# Optocoupler_STM32_REVB.net
KiCad netlist of a schematic drawn in Altium Designer
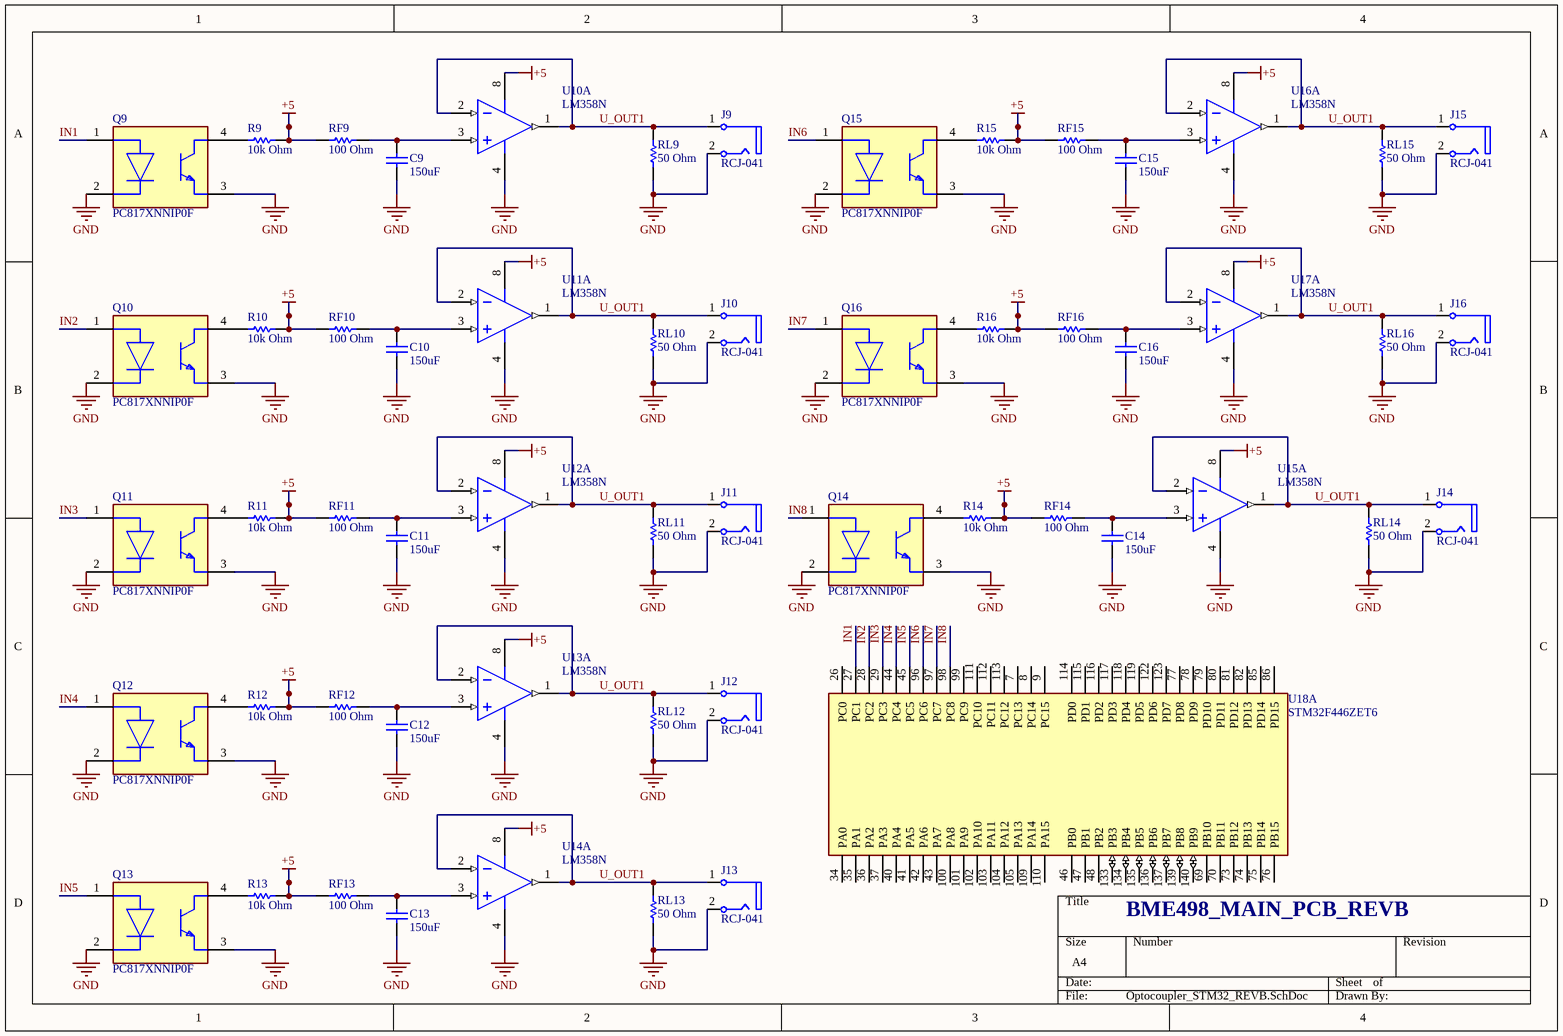
[diagram p0: Optocoupler_STM32_REVB.SchDoc]

(export (version "E")
  (design (tool "Eeschema 10.0.6"))
  (components
    (comp (ref "C9")
      (value "150uF")
      (footprint "RADIAL-0.1")
      (description "Capacitor")
      (fields
        (field (name "MANUFACTURER PART NUMBER") "EEA-GA1C150B")
        (field (name "PUBLISHER") "Altium Limited")
      )
      (libsource (lib "ECE295-Capacitors-TH") (part "CAP ALUM 15UF 20% 16V RADIAL"))
    )
    (comp (ref "C10")
      (value "150uF")
      (footprint "RADIAL-0.1")
      (description "Capacitor")
      (fields
        (field (name "MANUFACTURER PART NUMBER") "EEA-GA1C150B")
        (field (name "PUBLISHER") "Altium Limited")
      )
      (libsource (lib "ECE295-Capacitors-TH") (part "CAP ALUM 15UF 20% 16V RADIAL"))
    )
    (comp (ref "C11")
      (value "150uF")
      (footprint "RADIAL-0.1")
      (description "Capacitor")
      (fields
        (field (name "MANUFACTURER PART NUMBER") "EEA-GA1C150B")
        (field (name "PUBLISHER") "Altium Limited")
      )
      (libsource (lib "ECE295-Capacitors-TH") (part "CAP ALUM 15UF 20% 16V RADIAL"))
    )
    (comp (ref "C12")
      (value "150uF")
      (footprint "RADIAL-0.1")
      (description "Capacitor")
      (fields
        (field (name "MANUFACTURER PART NUMBER") "EEA-GA1C150B")
        (field (name "PUBLISHER") "Altium Limited")
      )
      (libsource (lib "ECE295-Capacitors-TH") (part "CAP ALUM 15UF 20% 16V RADIAL"))
    )
    (comp (ref "C13")
      (value "150uF")
      (footprint "RADIAL-0.1")
      (description "Capacitor")
      (fields
        (field (name "MANUFACTURER PART NUMBER") "EEA-GA1C150B")
        (field (name "PUBLISHER") "Altium Limited")
      )
      (libsource (lib "ECE295-Capacitors-TH") (part "CAP ALUM 15UF 20% 16V RADIAL"))
    )
    (comp (ref "C14")
      (value "150uF")
      (footprint "RADIAL-0.1")
      (description "Capacitor")
      (fields
        (field (name "MANUFACTURER PART NUMBER") "EEA-GA1C150B")
        (field (name "PUBLISHER") "Altium Limited")
      )
      (libsource (lib "ECE295-Capacitors-TH") (part "CAP ALUM 15UF 20% 16V RADIAL"))
    )
    (comp (ref "C15")
      (value "150uF")
      (footprint "RADIAL-0.1")
      (description "Capacitor")
      (fields
        (field (name "MANUFACTURER PART NUMBER") "EEA-GA1C150B")
        (field (name "PUBLISHER") "Altium Limited")
      )
      (libsource (lib "ECE295-Capacitors-TH") (part "CAP ALUM 15UF 20% 16V RADIAL"))
    )
    (comp (ref "C16")
      (value "150uF")
      (footprint "RADIAL-0.1")
      (description "Capacitor")
      (fields
        (field (name "MANUFACTURER PART NUMBER") "EEA-GA1C150B")
        (field (name "PUBLISHER") "Altium Limited")
      )
      (libsource (lib "ECE295-Capacitors-TH") (part "CAP ALUM 15UF 20% 16V RADIAL"))
    )
    (comp (ref "J9")
      (value "RCJ-041")
      (footprint "CUI-RCJ-041_V")
      (description "Female RCJ Jack, 2 Position, Height 11.724 mm, Tail Length 4 mm, RoHS, Bulk")
      (libsource (lib "Altium Content Vault") (part "JACK-2CD2"))
    )
    (comp (ref "J10")
      (value "RCJ-041")
      (footprint "CUI-RCJ-041_V")
      (description "Female RCJ Jack, 2 Position, Height 11.724 mm, Tail Length 4 mm, RoHS, Bulk")
      (libsource (lib "Altium Content Vault") (part "JACK-2CD2"))
    )
    (comp (ref "J11")
      (value "RCJ-041")
      (footprint "CUI-RCJ-041_V")
      (description "Female RCJ Jack, 2 Position, Height 11.724 mm, Tail Length 4 mm, RoHS, Bulk")
      (libsource (lib "Altium Content Vault") (part "JACK-2CD2"))
    )
    (comp (ref "J12")
      (value "RCJ-041")
      (footprint "CUI-RCJ-041_V")
      (description "Female RCJ Jack, 2 Position, Height 11.724 mm, Tail Length 4 mm, RoHS, Bulk")
      (libsource (lib "Altium Content Vault") (part "JACK-2CD2"))
    )
    (comp (ref "J13")
      (value "RCJ-041")
      (footprint "CUI-RCJ-041_V")
      (description "Female RCJ Jack, 2 Position, Height 11.724 mm, Tail Length 4 mm, RoHS, Bulk")
      (libsource (lib "Altium Content Vault") (part "JACK-2CD2"))
    )
    (comp (ref "J14")
      (value "RCJ-041")
      (footprint "CUI-RCJ-041_V")
      (description "Female RCJ Jack, 2 Position, Height 11.724 mm, Tail Length 4 mm, RoHS, Bulk")
      (libsource (lib "Altium Content Vault") (part "JACK-2CD2"))
    )
    (comp (ref "J15")
      (value "RCJ-041")
      (footprint "CUI-RCJ-041_V")
      (description "Female RCJ Jack, 2 Position, Height 11.724 mm, Tail Length 4 mm, RoHS, Bulk")
      (libsource (lib "Altium Content Vault") (part "JACK-2CD2"))
    )
    (comp (ref "J16")
      (value "RCJ-041")
      (footprint "CUI-RCJ-041_V")
      (description "Female RCJ Jack, 2 Position, Height 11.724 mm, Tail Length 4 mm, RoHS, Bulk")
      (libsource (lib "Altium Content Vault") (part "JACK-2CD2"))
    )
    (comp (ref "Q9")
      (value "PC817XNNIP0F")
      (footprint "FP-PC817XNNIP0F-MFG")
      (description "OPTOISOLATOR 5KV TRANS 4SMD")
      (libsource (lib "Altium Content Vault") (part "6470904bf6395c62928ee73e60120b8"))
    )
    (comp (ref "Q10")
      (value "PC817XNNIP0F")
      (footprint "FP-PC817XNNIP0F-MFG")
      (description "OPTOISOLATOR 5KV TRANS 4SMD")
      (libsource (lib "Altium Content Vault") (part "6470904bf6395c62928ee73e60120b8"))
    )
    (comp (ref "Q11")
      (value "PC817XNNIP0F")
      (footprint "FP-PC817XNNIP0F-MFG")
      (description "OPTOISOLATOR 5KV TRANS 4SMD")
      (libsource (lib "Altium Content Vault") (part "6470904bf6395c62928ee73e60120b8"))
    )
    (comp (ref "Q12")
      (value "PC817XNNIP0F")
      (footprint "FP-PC817XNNIP0F-MFG")
      (description "OPTOISOLATOR 5KV TRANS 4SMD")
      (libsource (lib "Altium Content Vault") (part "6470904bf6395c62928ee73e60120b8"))
    )
    (comp (ref "Q13")
      (value "PC817XNNIP0F")
      (footprint "FP-PC817XNNIP0F-MFG")
      (description "OPTOISOLATOR 5KV TRANS 4SMD")
      (libsource (lib "Altium Content Vault") (part "6470904bf6395c62928ee73e60120b8"))
    )
    (comp (ref "Q14")
      (value "PC817XNNIP0F")
      (footprint "FP-PC817XNNIP0F-MFG")
      (description "OPTOISOLATOR 5KV TRANS 4SMD")
      (libsource (lib "Altium Content Vault") (part "6470904bf6395c62928ee73e60120b8"))
    )
    (comp (ref "Q15")
      (value "PC817XNNIP0F")
      (footprint "FP-PC817XNNIP0F-MFG")
      (description "OPTOISOLATOR 5KV TRANS 4SMD")
      (libsource (lib "Altium Content Vault") (part "6470904bf6395c62928ee73e60120b8"))
    )
    (comp (ref "Q16")
      (value "PC817XNNIP0F")
      (footprint "FP-PC817XNNIP0F-MFG")
      (description "OPTOISOLATOR 5KV TRANS 4SMD")
      (libsource (lib "Altium Content Vault") (part "6470904bf6395c62928ee73e60120b8"))
    )
    (comp (ref "R9")
      (value "10k Ohm")
      (footprint "AXIAL-0.3")
      (description "Resistor")
      (fields
        (field (name "MANUFACTURER PART NUMBER") "CFR-25JB-52-10R")
        (field (name "TOLERANCE") "0.05")
        (field (name "PUBLISHER") "Altium Limited")
      )
      (libsource (lib "ECE295-Resistors-TH") (part "RES 10 OHM 5% 1/4W AXIAL"))
    )
    (comp (ref "R10")
      (value "10k Ohm")
      (footprint "AXIAL-0.3")
      (description "Resistor")
      (fields
        (field (name "MANUFACTURER PART NUMBER") "CFR-25JB-52-10R")
        (field (name "TOLERANCE") "0.05")
        (field (name "PUBLISHER") "Altium Limited")
      )
      (libsource (lib "ECE295-Resistors-TH") (part "RES 10 OHM 5% 1/4W AXIAL"))
    )
    (comp (ref "R11")
      (value "10k Ohm")
      (footprint "AXIAL-0.3")
      (description "Resistor")
      (fields
        (field (name "MANUFACTURER PART NUMBER") "CFR-25JB-52-10R")
        (field (name "TOLERANCE") "0.05")
        (field (name "PUBLISHER") "Altium Limited")
      )
      (libsource (lib "ECE295-Resistors-TH") (part "RES 10 OHM 5% 1/4W AXIAL"))
    )
    (comp (ref "R12")
      (value "10k Ohm")
      (footprint "AXIAL-0.3")
      (description "Resistor")
      (fields
        (field (name "MANUFACTURER PART NUMBER") "CFR-25JB-52-10R")
        (field (name "TOLERANCE") "0.05")
        (field (name "PUBLISHER") "Altium Limited")
      )
      (libsource (lib "ECE295-Resistors-TH") (part "RES 10 OHM 5% 1/4W AXIAL"))
    )
    (comp (ref "R13")
      (value "10k Ohm")
      (footprint "AXIAL-0.3")
      (description "Resistor")
      (fields
        (field (name "MANUFACTURER PART NUMBER") "CFR-25JB-52-10R")
        (field (name "TOLERANCE") "0.05")
        (field (name "PUBLISHER") "Altium Limited")
      )
      (libsource (lib "ECE295-Resistors-TH") (part "RES 10 OHM 5% 1/4W AXIAL"))
    )
    (comp (ref "R14")
      (value "10k Ohm")
      (footprint "AXIAL-0.3")
      (description "Resistor")
      (fields
        (field (name "MANUFACTURER PART NUMBER") "CFR-25JB-52-10R")
        (field (name "TOLERANCE") "0.05")
        (field (name "PUBLISHER") "Altium Limited")
      )
      (libsource (lib "ECE295-Resistors-TH") (part "RES 10 OHM 5% 1/4W AXIAL"))
    )
    (comp (ref "R15")
      (value "10k Ohm")
      (footprint "AXIAL-0.3")
      (description "Resistor")
      (fields
        (field (name "MANUFACTURER PART NUMBER") "CFR-25JB-52-10R")
        (field (name "TOLERANCE") "0.05")
        (field (name "PUBLISHER") "Altium Limited")
      )
      (libsource (lib "ECE295-Resistors-TH") (part "RES 10 OHM 5% 1/4W AXIAL"))
    )
    (comp (ref "R16")
      (value "10k Ohm")
      (footprint "AXIAL-0.3")
      (description "Resistor")
      (fields
        (field (name "MANUFACTURER PART NUMBER") "CFR-25JB-52-10R")
        (field (name "TOLERANCE") "0.05")
        (field (name "PUBLISHER") "Altium Limited")
      )
      (libsource (lib "ECE295-Resistors-TH") (part "RES 10 OHM 5% 1/4W AXIAL"))
    )
    (comp (ref "RF9")
      (value "100 Ohm")
      (footprint "AXIAL-0.3")
      (description "Resistor")
      (fields
        (field (name "MANUFACTURER PART NUMBER") "CFR-25JB-52-10R")
        (field (name "TOLERANCE") "0.05")
        (field (name "PUBLISHER") "Altium Limited")
      )
      (libsource (lib "ECE295-Resistors-TH") (part "RES 10 OHM 5% 1/4W AXIAL"))
    )
    (comp (ref "RF10")
      (value "100 Ohm")
      (footprint "AXIAL-0.3")
      (description "Resistor")
      (fields
        (field (name "MANUFACTURER PART NUMBER") "CFR-25JB-52-10R")
        (field (name "TOLERANCE") "0.05")
        (field (name "PUBLISHER") "Altium Limited")
      )
      (libsource (lib "ECE295-Resistors-TH") (part "RES 10 OHM 5% 1/4W AXIAL"))
    )
    (comp (ref "RF11")
      (value "100 Ohm")
      (footprint "AXIAL-0.3")
      (description "Resistor")
      (fields
        (field (name "MANUFACTURER PART NUMBER") "CFR-25JB-52-10R")
        (field (name "TOLERANCE") "0.05")
        (field (name "PUBLISHER") "Altium Limited")
      )
      (libsource (lib "ECE295-Resistors-TH") (part "RES 10 OHM 5% 1/4W AXIAL"))
    )
    (comp (ref "RF12")
      (value "100 Ohm")
      (footprint "AXIAL-0.3")
      (description "Resistor")
      (fields
        (field (name "MANUFACTURER PART NUMBER") "CFR-25JB-52-10R")
        (field (name "TOLERANCE") "0.05")
        (field (name "PUBLISHER") "Altium Limited")
      )
      (libsource (lib "ECE295-Resistors-TH") (part "RES 10 OHM 5% 1/4W AXIAL"))
    )
    (comp (ref "RF13")
      (value "100 Ohm")
      (footprint "AXIAL-0.3")
      (description "Resistor")
      (fields
        (field (name "MANUFACTURER PART NUMBER") "CFR-25JB-52-10R")
        (field (name "TOLERANCE") "0.05")
        (field (name "PUBLISHER") "Altium Limited")
      )
      (libsource (lib "ECE295-Resistors-TH") (part "RES 10 OHM 5% 1/4W AXIAL"))
    )
    (comp (ref "RF14")
      (value "100 Ohm")
      (footprint "AXIAL-0.3")
      (description "Resistor")
      (fields
        (field (name "MANUFACTURER PART NUMBER") "CFR-25JB-52-10R")
        (field (name "TOLERANCE") "0.05")
        (field (name "PUBLISHER") "Altium Limited")
      )
      (libsource (lib "ECE295-Resistors-TH") (part "RES 10 OHM 5% 1/4W AXIAL"))
    )
    (comp (ref "RF15")
      (value "100 Ohm")
      (footprint "AXIAL-0.3")
      (description "Resistor")
      (fields
        (field (name "MANUFACTURER PART NUMBER") "CFR-25JB-52-10R")
        (field (name "TOLERANCE") "0.05")
        (field (name "PUBLISHER") "Altium Limited")
      )
      (libsource (lib "ECE295-Resistors-TH") (part "RES 10 OHM 5% 1/4W AXIAL"))
    )
    (comp (ref "RF16")
      (value "100 Ohm")
      (footprint "AXIAL-0.3")
      (description "Resistor")
      (fields
        (field (name "MANUFACTURER PART NUMBER") "CFR-25JB-52-10R")
        (field (name "TOLERANCE") "0.05")
        (field (name "PUBLISHER") "Altium Limited")
      )
      (libsource (lib "ECE295-Resistors-TH") (part "RES 10 OHM 5% 1/4W AXIAL"))
    )
    (comp (ref "RL9")
      (value "50 Ohm")
      (footprint "AXIAL-0.3")
      (description "Resistor")
      (fields
        (field (name "MANUFACTURER PART NUMBER") "CFR-25JB-52-10R")
        (field (name "TOLERANCE") "0.05")
        (field (name "PUBLISHER") "Altium Limited")
      )
      (libsource (lib "ECE295-Resistors-TH") (part "RES 10 OHM 5% 1/4W AXIAL"))
    )
    (comp (ref "RL10")
      (value "50 Ohm")
      (footprint "AXIAL-0.3")
      (description "Resistor")
      (fields
        (field (name "MANUFACTURER PART NUMBER") "CFR-25JB-52-10R")
        (field (name "TOLERANCE") "0.05")
        (field (name "PUBLISHER") "Altium Limited")
      )
      (libsource (lib "ECE295-Resistors-TH") (part "RES 10 OHM 5% 1/4W AXIAL"))
    )
    (comp (ref "RL11")
      (value "50 Ohm")
      (footprint "AXIAL-0.3")
      (description "Resistor")
      (fields
        (field (name "MANUFACTURER PART NUMBER") "CFR-25JB-52-10R")
        (field (name "TOLERANCE") "0.05")
        (field (name "PUBLISHER") "Altium Limited")
      )
      (libsource (lib "ECE295-Resistors-TH") (part "RES 10 OHM 5% 1/4W AXIAL"))
    )
    (comp (ref "RL12")
      (value "50 Ohm")
      (footprint "AXIAL-0.3")
      (description "Resistor")
      (fields
        (field (name "MANUFACTURER PART NUMBER") "CFR-25JB-52-10R")
        (field (name "TOLERANCE") "0.05")
        (field (name "PUBLISHER") "Altium Limited")
      )
      (libsource (lib "ECE295-Resistors-TH") (part "RES 10 OHM 5% 1/4W AXIAL"))
    )
    (comp (ref "RL13")
      (value "50 Ohm")
      (footprint "AXIAL-0.3")
      (description "Resistor")
      (fields
        (field (name "MANUFACTURER PART NUMBER") "CFR-25JB-52-10R")
        (field (name "TOLERANCE") "0.05")
        (field (name "PUBLISHER") "Altium Limited")
      )
      (libsource (lib "ECE295-Resistors-TH") (part "RES 10 OHM 5% 1/4W AXIAL"))
    )
    (comp (ref "RL14")
      (value "50 Ohm")
      (footprint "AXIAL-0.3")
      (description "Resistor")
      (fields
        (field (name "MANUFACTURER PART NUMBER") "CFR-25JB-52-10R")
        (field (name "TOLERANCE") "0.05")
        (field (name "PUBLISHER") "Altium Limited")
      )
      (libsource (lib "ECE295-Resistors-TH") (part "RES 10 OHM 5% 1/4W AXIAL"))
    )
    (comp (ref "RL15")
      (value "50 Ohm")
      (footprint "AXIAL-0.3")
      (description "Resistor")
      (fields
        (field (name "MANUFACTURER PART NUMBER") "CFR-25JB-52-10R")
        (field (name "TOLERANCE") "0.05")
        (field (name "PUBLISHER") "Altium Limited")
      )
      (libsource (lib "ECE295-Resistors-TH") (part "RES 10 OHM 5% 1/4W AXIAL"))
    )
    (comp (ref "RL16")
      (value "50 Ohm")
      (footprint "AXIAL-0.3")
      (description "Resistor")
      (fields
        (field (name "MANUFACTURER PART NUMBER") "CFR-25JB-52-10R")
        (field (name "TOLERANCE") "0.05")
        (field (name "PUBLISHER") "Altium Limited")
      )
      (libsource (lib "ECE295-Resistors-TH") (part "RES 10 OHM 5% 1/4W AXIAL"))
    )
    (comp (ref "U10")
      (value "LM358N")
      (footprint "ONSC-PDIP-8-626-05_M")
      (description "Single Supply Dual Operational Amplifier, 3 to 32 V, 0 to 70 degC, 8-Pin PDIP, Tube")
      (fields (field (name "MANUFACTURER") "On Semiconductor"))
      (libsource (lib "Altium Content Vault") (part "ONSC-LM358_NCV2904-8"))
    )
    (comp (ref "U11")
      (value "LM358N")
      (footprint "ONSC-PDIP-8-626-05_M")
      (description "Single Supply Dual Operational Amplifier, 3 to 32 V, 0 to 70 degC, 8-Pin PDIP, Tube")
      (fields (field (name "MANUFACTURER") "On Semiconductor"))
      (libsource (lib "Altium Content Vault") (part "ONSC-LM358_NCV2904-8"))
    )
    (comp (ref "U12")
      (value "LM358N")
      (footprint "ONSC-PDIP-8-626-05_M")
      (description "Single Supply Dual Operational Amplifier, 3 to 32 V, 0 to 70 degC, 8-Pin PDIP, Tube")
      (fields (field (name "MANUFACTURER") "On Semiconductor"))
      (libsource (lib "Altium Content Vault") (part "ONSC-LM358_NCV2904-8"))
    )
    (comp (ref "U13")
      (value "LM358N")
      (footprint "ONSC-PDIP-8-626-05_M")
      (description "Single Supply Dual Operational Amplifier, 3 to 32 V, 0 to 70 degC, 8-Pin PDIP, Tube")
      (fields (field (name "MANUFACTURER") "On Semiconductor"))
      (libsource (lib "Altium Content Vault") (part "ONSC-LM358_NCV2904-8"))
    )
    (comp (ref "U14")
      (value "LM358N")
      (footprint "ONSC-PDIP-8-626-05_M")
      (description "Single Supply Dual Operational Amplifier, 3 to 32 V, 0 to 70 degC, 8-Pin PDIP, Tube")
      (fields (field (name "MANUFACTURER") "On Semiconductor"))
      (libsource (lib "Altium Content Vault") (part "ONSC-LM358_NCV2904-8"))
    )
    (comp (ref "U15")
      (value "LM358N")
      (footprint "ONSC-PDIP-8-626-05_M")
      (description "Single Supply Dual Operational Amplifier, 3 to 32 V, 0 to 70 degC, 8-Pin PDIP, Tube")
      (fields (field (name "MANUFACTURER") "On Semiconductor"))
      (libsource (lib "Altium Content Vault") (part "ONSC-LM358_NCV2904-8"))
    )
    (comp (ref "U16")
      (value "LM358N")
      (footprint "ONSC-PDIP-8-626-05_M")
      (description "Single Supply Dual Operational Amplifier, 3 to 32 V, 0 to 70 degC, 8-Pin PDIP, Tube")
      (fields (field (name "MANUFACTURER") "On Semiconductor"))
      (libsource (lib "Altium Content Vault") (part "ONSC-LM358_NCV2904-8"))
    )
    (comp (ref "U17")
      (value "LM358N")
      (footprint "ONSC-PDIP-8-626-05_M")
      (description "Single Supply Dual Operational Amplifier, 3 to 32 V, 0 to 70 degC, 8-Pin PDIP, Tube")
      (fields (field (name "MANUFACTURER") "On Semiconductor"))
      (libsource (lib "Altium Content Vault") (part "ONSC-LM358_NCV2904-8"))
    )
    (comp (ref "U18")
      (value "STM32F446ZET6")
      (footprint "FP-STM32F446ZET6-MFG")
      (description "IC MCU 32BIT 512KB FLASH 144LQFP")
      (fields
        (field (name "OCTOPART") "https://octopart.com/stm32f446zet6-stmicroelectronics-52642927")
        (field (name "MANUFACTURER") "STMicroelectronics")
      )
      (libsource (lib "Altium Content Vault") (part "a0fab8d4e0431f78458e0514a03e2d2"))
    )
  )
  (nets
    (net (code "1") (name "+5") (class "Default")
      (node (ref "R10") (pin "2") (pinfunction "2_2") (pintype "passive"))
      (node (ref "R11") (pin "2") (pinfunction "2_2") (pintype "passive"))
      (node (ref "R12") (pin "2") (pinfunction "2_2") (pintype "passive"))
      (node (ref "R13") (pin "2") (pinfunction "2_2") (pintype "passive"))
      (node (ref "R14") (pin "2") (pinfunction "2_2") (pintype "passive"))
      (node (ref "R15") (pin "2") (pinfunction "2_2") (pintype "passive"))
      (node (ref "R16") (pin "2") (pinfunction "2_2") (pintype "passive"))
      (node (ref "R9") (pin "2") (pinfunction "2_2") (pintype "passive"))
      (node (ref "RF10") (pin "1") (pinfunction "1_1") (pintype "passive"))
      (node (ref "RF11") (pin "1") (pinfunction "1_1") (pintype "passive"))
      (node (ref "RF12") (pin "1") (pinfunction "1_1") (pintype "passive"))
      (node (ref "RF13") (pin "1") (pinfunction "1_1") (pintype "passive"))
      (node (ref "RF14") (pin "1") (pinfunction "1_1") (pintype "passive"))
      (node (ref "RF15") (pin "1") (pinfunction "1_1") (pintype "passive"))
      (node (ref "RF16") (pin "1") (pinfunction "1_1") (pintype "passive"))
      (node (ref "RF9") (pin "1") (pinfunction "1_1") (pintype "passive"))
      (node (ref "U10") (pin "8") (pinfunction "VCC_8") (pintype "power_in"))
      (node (ref "U11") (pin "8") (pinfunction "VCC_8") (pintype "power_in"))
      (node (ref "U12") (pin "8") (pinfunction "VCC_8") (pintype "power_in"))
      (node (ref "U13") (pin "8") (pinfunction "VCC_8") (pintype "power_in"))
      (node (ref "U14") (pin "8") (pinfunction "VCC_8") (pintype "power_in"))
      (node (ref "U15") (pin "8") (pinfunction "VCC_8") (pintype "power_in"))
      (node (ref "U16") (pin "8") (pinfunction "VCC_8") (pintype "power_in"))
      (node (ref "U17") (pin "8") (pinfunction "VCC_8") (pintype "power_in"))
    )
    (net (code "2") (name "/IN1") (class "Default")
      (node (ref "Q9") (pin "1") (pinfunction "A_1") (pintype "passive"))
      (node (ref "U18") (pin "27") (pinfunction "PC1_27") (pintype "passive"))
    )
    (net (code "3") (name "/IN2") (class "Default")
      (node (ref "Q10") (pin "1") (pinfunction "A_1") (pintype "passive"))
      (node (ref "U18") (pin "28") (pinfunction "PC2_28") (pintype "passive"))
    )
    (net (code "4") (name "/IN3") (class "Default")
      (node (ref "Q11") (pin "1") (pinfunction "A_1") (pintype "passive"))
      (node (ref "U18") (pin "29") (pinfunction "PC3_29") (pintype "passive"))
    )
    (net (code "5") (name "/IN4") (class "Default")
      (node (ref "Q12") (pin "1") (pinfunction "A_1") (pintype "passive"))
      (node (ref "U18") (pin "44") (pinfunction "PC4_44") (pintype "passive"))
    )
    (net (code "6") (name "/IN5") (class "Default")
      (node (ref "Q13") (pin "1") (pinfunction "A_1") (pintype "passive"))
      (node (ref "U18") (pin "45") (pinfunction "PC5_45") (pintype "passive"))
    )
    (net (code "7") (name "/IN6") (class "Default")
      (node (ref "Q15") (pin "1") (pinfunction "A_1") (pintype "passive"))
      (node (ref "U18") (pin "96") (pinfunction "PC6_96") (pintype "passive"))
    )
    (net (code "8") (name "/IN7") (class "Default")
      (node (ref "Q16") (pin "1") (pinfunction "A_1") (pintype "passive"))
      (node (ref "U18") (pin "97") (pinfunction "PC7_97") (pintype "passive"))
    )
    (net (code "9") (name "/IN8") (class "Default")
      (node (ref "Q14") (pin "1") (pinfunction "A_1") (pintype "passive"))
      (node (ref "U18") (pin "98") (pinfunction "PC8_98") (pintype "passive"))
    )
    (net (code "10") (name "/U_OUT1") (class "Default")
      (node (ref "J10") (pin "1") (pinfunction "1_1") (pintype "passive"))
      (node (ref "J11") (pin "1") (pinfunction "1_1") (pintype "passive"))
      (node (ref "J12") (pin "1") (pinfunction "1_1") (pintype "passive"))
      (node (ref "J13") (pin "1") (pinfunction "1_1") (pintype "passive"))
      (node (ref "J14") (pin "1") (pinfunction "1_1") (pintype "passive"))
      (node (ref "J15") (pin "1") (pinfunction "1_1") (pintype "passive"))
      (node (ref "J16") (pin "1") (pinfunction "1_1") (pintype "passive"))
      (node (ref "J9") (pin "1") (pinfunction "1_1") (pintype "passive"))
      (node (ref "RL10") (pin "2") (pinfunction "2_2") (pintype "passive"))
      (node (ref "RL11") (pin "2") (pinfunction "2_2") (pintype "passive"))
      (node (ref "RL12") (pin "2") (pinfunction "2_2") (pintype "passive"))
      (node (ref "RL13") (pin "2") (pinfunction "2_2") (pintype "passive"))
      (node (ref "RL14") (pin "2") (pinfunction "2_2") (pintype "passive"))
      (node (ref "RL15") (pin "2") (pinfunction "2_2") (pintype "passive"))
      (node (ref "RL16") (pin "2") (pinfunction "2_2") (pintype "passive"))
      (node (ref "RL9") (pin "2") (pinfunction "2_2") (pintype "passive"))
      (node (ref "U10") (pin "1") (pinfunction "OUTA_1") (pintype "output"))
      (node (ref "U10") (pin "2") (pinfunction "INA-_2") (pintype "input"))
      (node (ref "U11") (pin "1") (pinfunction "OUTA_1") (pintype "output"))
      (node (ref "U11") (pin "2") (pinfunction "INA-_2") (pintype "input"))
      (node (ref "U12") (pin "1") (pinfunction "OUTA_1") (pintype "output"))
      (node (ref "U12") (pin "2") (pinfunction "INA-_2") (pintype "input"))
      (node (ref "U13") (pin "1") (pinfunction "OUTA_1") (pintype "output"))
      (node (ref "U13") (pin "2") (pinfunction "INA-_2") (pintype "input"))
      (node (ref "U14") (pin "1") (pinfunction "OUTA_1") (pintype "output"))
      (node (ref "U14") (pin "2") (pinfunction "INA-_2") (pintype "input"))
      (node (ref "U15") (pin "1") (pinfunction "OUTA_1") (pintype "output"))
      (node (ref "U15") (pin "2") (pinfunction "INA-_2") (pintype "input"))
      (node (ref "U16") (pin "1") (pinfunction "OUTA_1") (pintype "output"))
      (node (ref "U16") (pin "2") (pinfunction "INA-_2") (pintype "input"))
      (node (ref "U17") (pin "1") (pinfunction "OUTA_1") (pintype "output"))
      (node (ref "U17") (pin "2") (pinfunction "INA-_2") (pintype "input"))
    )
    (net (code "11") (name "GND") (class "Default")
      (node (ref "C10") (pin "1") (pinfunction "1_1") (pintype "passive"))
      (node (ref "C11") (pin "1") (pinfunction "1_1") (pintype "passive"))
      (node (ref "C12") (pin "1") (pinfunction "1_1") (pintype "passive"))
      (node (ref "C13") (pin "1") (pinfunction "1_1") (pintype "passive"))
      (node (ref "C14") (pin "1") (pinfunction "1_1") (pintype "passive"))
      (node (ref "C15") (pin "1") (pinfunction "1_1") (pintype "passive"))
      (node (ref "C16") (pin "1") (pinfunction "1_1") (pintype "passive"))
      (node (ref "C9") (pin "1") (pinfunction "1_1") (pintype "passive"))
      (node (ref "J10") (pin "2") (pinfunction "2_2") (pintype "passive"))
      (node (ref "J11") (pin "2") (pinfunction "2_2") (pintype "passive"))
      (node (ref "J12") (pin "2") (pinfunction "2_2") (pintype "passive"))
      (node (ref "J13") (pin "2") (pinfunction "2_2") (pintype "passive"))
      (node (ref "J14") (pin "2") (pinfunction "2_2") (pintype "passive"))
      (node (ref "J15") (pin "2") (pinfunction "2_2") (pintype "passive"))
      (node (ref "J16") (pin "2") (pinfunction "2_2") (pintype "passive"))
      (node (ref "J9") (pin "2") (pinfunction "2_2") (pintype "passive"))
      (node (ref "Q10") (pin "2") (pinfunction "C_2") (pintype "passive"))
      (node (ref "Q10") (pin "3") (pinfunction "E_3") (pintype "passive"))
      (node (ref "Q11") (pin "2") (pinfunction "C_2") (pintype "passive"))
      (node (ref "Q11") (pin "3") (pinfunction "E_3") (pintype "passive"))
      (node (ref "Q12") (pin "2") (pinfunction "C_2") (pintype "passive"))
      (node (ref "Q12") (pin "3") (pinfunction "E_3") (pintype "passive"))
      (node (ref "Q13") (pin "2") (pinfunction "C_2") (pintype "passive"))
      (node (ref "Q13") (pin "3") (pinfunction "E_3") (pintype "passive"))
      (node (ref "Q14") (pin "2") (pinfunction "C_2") (pintype "passive"))
      (node (ref "Q14") (pin "3") (pinfunction "E_3") (pintype "passive"))
      (node (ref "Q15") (pin "2") (pinfunction "C_2") (pintype "passive"))
      (node (ref "Q15") (pin "3") (pinfunction "E_3") (pintype "passive"))
      (node (ref "Q16") (pin "2") (pinfunction "C_2") (pintype "passive"))
      (node (ref "Q16") (pin "3") (pinfunction "E_3") (pintype "passive"))
      (node (ref "Q9") (pin "2") (pinfunction "C_2") (pintype "passive"))
      (node (ref "Q9") (pin "3") (pinfunction "E_3") (pintype "passive"))
      (node (ref "RL10") (pin "1") (pinfunction "1_1") (pintype "passive"))
      (node (ref "RL11") (pin "1") (pinfunction "1_1") (pintype "passive"))
      (node (ref "RL12") (pin "1") (pinfunction "1_1") (pintype "passive"))
      (node (ref "RL13") (pin "1") (pinfunction "1_1") (pintype "passive"))
      (node (ref "RL14") (pin "1") (pinfunction "1_1") (pintype "passive"))
      (node (ref "RL15") (pin "1") (pinfunction "1_1") (pintype "passive"))
      (node (ref "RL16") (pin "1") (pinfunction "1_1") (pintype "passive"))
      (node (ref "RL9") (pin "1") (pinfunction "1_1") (pintype "passive"))
      (node (ref "U10") (pin "4") (pinfunction "VEE/GND_4") (pintype "power_in"))
      (node (ref "U11") (pin "4") (pinfunction "VEE/GND_4") (pintype "power_in"))
      (node (ref "U12") (pin "4") (pinfunction "VEE/GND_4") (pintype "power_in"))
      (node (ref "U13") (pin "4") (pinfunction "VEE/GND_4") (pintype "power_in"))
      (node (ref "U14") (pin "4") (pinfunction "VEE/GND_4") (pintype "power_in"))
      (node (ref "U15") (pin "4") (pinfunction "VEE/GND_4") (pintype "power_in"))
      (node (ref "U16") (pin "4") (pinfunction "VEE/GND_4") (pintype "power_in"))
      (node (ref "U17") (pin "4") (pinfunction "VEE/GND_4") (pintype "power_in"))
    )
    (net (code "12") (name "Net-(Q9-C-Pad4)") (class "Default")
      (node (ref "Q9") (pin "4") (pinfunction "C_4") (pintype "passive"))
      (node (ref "R9") (pin "1") (pinfunction "1_1") (pintype "passive"))
    )
    (net (code "13") (name "Net-(Q10-C-Pad4)") (class "Default")
      (node (ref "Q10") (pin "4") (pinfunction "C_4") (pintype "passive"))
      (node (ref "R10") (pin "1") (pinfunction "1_1") (pintype "passive"))
    )
    (net (code "14") (name "Net-(Q11-C-Pad4)") (class "Default")
      (node (ref "Q11") (pin "4") (pinfunction "C_4") (pintype "passive"))
      (node (ref "R11") (pin "1") (pinfunction "1_1") (pintype "passive"))
    )
    (net (code "15") (name "Net-(Q12-C-Pad4)") (class "Default")
      (node (ref "Q12") (pin "4") (pinfunction "C_4") (pintype "passive"))
      (node (ref "R12") (pin "1") (pinfunction "1_1") (pintype "passive"))
    )
    (net (code "16") (name "Net-(Q13-C-Pad4)") (class "Default")
      (node (ref "Q13") (pin "4") (pinfunction "C_4") (pintype "passive"))
      (node (ref "R13") (pin "1") (pinfunction "1_1") (pintype "passive"))
    )
    (net (code "17") (name "Net-(Q14-C-Pad4)") (class "Default")
      (node (ref "Q14") (pin "4") (pinfunction "C_4") (pintype "passive"))
      (node (ref "R14") (pin "1") (pinfunction "1_1") (pintype "passive"))
    )
    (net (code "18") (name "Net-(Q15-C-Pad4)") (class "Default")
      (node (ref "Q15") (pin "4") (pinfunction "C_4") (pintype "passive"))
      (node (ref "R15") (pin "1") (pinfunction "1_1") (pintype "passive"))
    )
    (net (code "19") (name "Net-(Q16-C-Pad4)") (class "Default")
      (node (ref "Q16") (pin "4") (pinfunction "C_4") (pintype "passive"))
      (node (ref "R16") (pin "1") (pinfunction "1_1") (pintype "passive"))
    )
    (net (code "20") (name "Net-(U10A-INA+)") (class "Default")
      (node (ref "C9") (pin "2") (pinfunction "2_2") (pintype "passive"))
      (node (ref "RF9") (pin "2") (pinfunction "2_2") (pintype "passive"))
      (node (ref "U10") (pin "3") (pinfunction "INA+_3") (pintype "input"))
    )
    (net (code "21") (name "Net-(U11A-INA+)") (class "Default")
      (node (ref "C10") (pin "2") (pinfunction "2_2") (pintype "passive"))
      (node (ref "RF10") (pin "2") (pinfunction "2_2") (pintype "passive"))
      (node (ref "U11") (pin "3") (pinfunction "INA+_3") (pintype "input"))
    )
    (net (code "22") (name "Net-(U12A-INA+)") (class "Default")
      (node (ref "C11") (pin "2") (pinfunction "2_2") (pintype "passive"))
      (node (ref "RF11") (pin "2") (pinfunction "2_2") (pintype "passive"))
      (node (ref "U12") (pin "3") (pinfunction "INA+_3") (pintype "input"))
    )
    (net (code "23") (name "Net-(U13A-INA+)") (class "Default")
      (node (ref "C12") (pin "2") (pinfunction "2_2") (pintype "passive"))
      (node (ref "RF12") (pin "2") (pinfunction "2_2") (pintype "passive"))
      (node (ref "U13") (pin "3") (pinfunction "INA+_3") (pintype "input"))
    )
    (net (code "24") (name "Net-(U14A-INA+)") (class "Default")
      (node (ref "C13") (pin "2") (pinfunction "2_2") (pintype "passive"))
      (node (ref "RF13") (pin "2") (pinfunction "2_2") (pintype "passive"))
      (node (ref "U14") (pin "3") (pinfunction "INA+_3") (pintype "input"))
    )
    (net (code "25") (name "Net-(U15A-INA+)") (class "Default")
      (node (ref "C14") (pin "2") (pinfunction "2_2") (pintype "passive"))
      (node (ref "RF14") (pin "2") (pinfunction "2_2") (pintype "passive"))
      (node (ref "U15") (pin "3") (pinfunction "INA+_3") (pintype "input"))
    )
    (net (code "26") (name "Net-(U16A-INA+)") (class "Default")
      (node (ref "C15") (pin "2") (pinfunction "2_2") (pintype "passive"))
      (node (ref "RF15") (pin "2") (pinfunction "2_2") (pintype "passive"))
      (node (ref "U16") (pin "3") (pinfunction "INA+_3") (pintype "input"))
    )
    (net (code "27") (name "Net-(U17A-INA+)") (class "Default")
      (node (ref "C16") (pin "2") (pinfunction "2_2") (pintype "passive"))
      (node (ref "RF16") (pin "2") (pinfunction "2_2") (pintype "passive"))
      (node (ref "U17") (pin "3") (pinfunction "INA+_3") (pintype "input"))
    )
    (net (code "28") (name "unconnected-(U18A-PA0-Pad34)") (class "Default")
      (node (ref "U18") (pin "34") (pinfunction "PA0_34") (pintype "passive"))
    )
    (net (code "29") (name "unconnected-(U18A-PA1-Pad35)") (class "Default")
      (node (ref "U18") (pin "35") (pinfunction "PA1_35") (pintype "passive"))
    )
    (net (code "30") (name "unconnected-(U18A-PA2-Pad36)") (class "Default")
      (node (ref "U18") (pin "36") (pinfunction "PA2_36") (pintype "passive"))
    )
    (net (code "31") (name "unconnected-(U18A-PA3-Pad37)") (class "Default")
      (node (ref "U18") (pin "37") (pinfunction "PA3_37") (pintype "passive"))
    )
    (net (code "32") (name "unconnected-(U18A-PA4-Pad40)") (class "Default")
      (node (ref "U18") (pin "40") (pinfunction "PA4_40") (pintype "passive"))
    )
    (net (code "33") (name "unconnected-(U18A-PA5-Pad41)") (class "Default")
      (node (ref "U18") (pin "41") (pinfunction "PA5_41") (pintype "passive"))
    )
    (net (code "34") (name "unconnected-(U18A-PA6-Pad42)") (class "Default")
      (node (ref "U18") (pin "42") (pinfunction "PA6_42") (pintype "passive"))
    )
    (net (code "35") (name "unconnected-(U18A-PA7-Pad43)") (class "Default")
      (node (ref "U18") (pin "43") (pinfunction "PA7_43") (pintype "passive"))
    )
    (net (code "36") (name "unconnected-(U18A-PA8-Pad100)") (class "Default")
      (node (ref "U18") (pin "100") (pinfunction "PA8_100") (pintype "passive"))
    )
    (net (code "37") (name "unconnected-(U18A-PA9-Pad101)") (class "Default")
      (node (ref "U18") (pin "101") (pinfunction "PA9_101") (pintype "passive"))
    )
    (net (code "38") (name "unconnected-(U18A-PA10-Pad102)") (class "Default")
      (node (ref "U18") (pin "102") (pinfunction "PA10_102") (pintype "passive"))
    )
    (net (code "39") (name "unconnected-(U18A-PA11-Pad103)") (class "Default")
      (node (ref "U18") (pin "103") (pinfunction "PA11_103") (pintype "passive"))
    )
    (net (code "40") (name "unconnected-(U18A-PA12-Pad104)") (class "Default")
      (node (ref "U18") (pin "104") (pinfunction "PA12_104") (pintype "passive"))
    )
    (net (code "41") (name "unconnected-(U18A-PA13-Pad105)") (class "Default")
      (node (ref "U18") (pin "105") (pinfunction "PA13_105") (pintype "passive"))
    )
    (net (code "42") (name "unconnected-(U18A-PA14-Pad109)") (class "Default")
      (node (ref "U18") (pin "109") (pinfunction "PA14_109") (pintype "passive"))
    )
    (net (code "43") (name "unconnected-(U18A-PA15-Pad110)") (class "Default")
      (node (ref "U18") (pin "110") (pinfunction "PA15_110") (pintype "passive"))
    )
    (net (code "44") (name "unconnected-(U18A-PB0-Pad46)") (class "Default")
      (node (ref "U18") (pin "46") (pinfunction "PB0_46") (pintype "passive"))
    )
    (net (code "45") (name "unconnected-(U18A-PB1-Pad47)") (class "Default")
      (node (ref "U18") (pin "47") (pinfunction "PB1_47") (pintype "passive"))
    )
    (net (code "46") (name "unconnected-(U18A-PB2-Pad48)") (class "Default")
      (node (ref "U18") (pin "48") (pinfunction "PB2_48") (pintype "passive"))
    )
    (net (code "47") (name "unconnected-(U18A-PB3-Pad133)") (class "Default")
      (node (ref "U18") (pin "133") (pinfunction "PB3_133") (pintype "bidirectional"))
    )
    (net (code "48") (name "unconnected-(U18A-PB4-Pad134)") (class "Default")
      (node (ref "U18") (pin "134") (pinfunction "PB4_134") (pintype "bidirectional"))
    )
    (net (code "49") (name "unconnected-(U18A-PB5-Pad135)") (class "Default")
      (node (ref "U18") (pin "135") (pinfunction "PB5_135") (pintype "bidirectional"))
    )
    (net (code "50") (name "unconnected-(U18A-PB6-Pad136)") (class "Default")
      (node (ref "U18") (pin "136") (pinfunction "PB6_136") (pintype "bidirectional"))
    )
    (net (code "51") (name "unconnected-(U18A-PB7-Pad137)") (class "Default")
      (node (ref "U18") (pin "137") (pinfunction "PB7_137") (pintype "bidirectional"))
    )
    (net (code "52") (name "unconnected-(U18A-PB8-Pad139)") (class "Default")
      (node (ref "U18") (pin "139") (pinfunction "PB8_139") (pintype "bidirectional"))
    )
    (net (code "53") (name "unconnected-(U18A-PB9-Pad140)") (class "Default")
      (node (ref "U18") (pin "140") (pinfunction "PB9_140") (pintype "bidirectional"))
    )
    (net (code "54") (name "unconnected-(U18A-PB10-Pad69)") (class "Default")
      (node (ref "U18") (pin "69") (pinfunction "PB10_69") (pintype "passive"))
    )
    (net (code "55") (name "unconnected-(U18A-PB11-Pad70)") (class "Default")
      (node (ref "U18") (pin "70") (pinfunction "PB11_70") (pintype "passive"))
    )
    (net (code "56") (name "unconnected-(U18A-PB12-Pad73)") (class "Default")
      (node (ref "U18") (pin "73") (pinfunction "PB12_73") (pintype "passive"))
    )
    (net (code "57") (name "unconnected-(U18A-PB13-Pad74)") (class "Default")
      (node (ref "U18") (pin "74") (pinfunction "PB13_74") (pintype "passive"))
    )
    (net (code "58") (name "unconnected-(U18A-PB14-Pad75)") (class "Default")
      (node (ref "U18") (pin "75") (pinfunction "PB14_75") (pintype "passive"))
    )
    (net (code "59") (name "unconnected-(U18A-PB15-Pad76)") (class "Default")
      (node (ref "U18") (pin "76") (pinfunction "PB15_76") (pintype "passive"))
    )
    (net (code "60") (name "unconnected-(U18A-PC0-Pad26)") (class "Default")
      (node (ref "U18") (pin "26") (pinfunction "PC0_26") (pintype "passive"))
    )
    (net (code "61") (name "unconnected-(U18A-PC9-Pad99)") (class "Default")
      (node (ref "U18") (pin "99") (pinfunction "PC9_99") (pintype "passive"))
    )
    (net (code "62") (name "unconnected-(U18A-PC10-Pad111)") (class "Default")
      (node (ref "U18") (pin "111") (pinfunction "PC10_111") (pintype "passive"))
    )
    (net (code "63") (name "unconnected-(U18A-PC11-Pad112)") (class "Default")
      (node (ref "U18") (pin "112") (pinfunction "PC11_112") (pintype "passive"))
    )
    (net (code "64") (name "unconnected-(U18A-PC12-Pad113)") (class "Default")
      (node (ref "U18") (pin "113") (pinfunction "PC12_113") (pintype "passive"))
    )
    (net (code "65") (name "unconnected-(U18A-PC13-Pad7)") (class "Default")
      (node (ref "U18") (pin "7") (pinfunction "PC13_7") (pintype "passive"))
    )
    (net (code "66") (name "unconnected-(U18A-PC14-Pad8)") (class "Default")
      (node (ref "U18") (pin "8") (pinfunction "PC14_8") (pintype "passive"))
    )
    (net (code "67") (name "unconnected-(U18A-PC15-Pad9)") (class "Default")
      (node (ref "U18") (pin "9") (pinfunction "PC15_9") (pintype "passive"))
    )
    (net (code "68") (name "unconnected-(U18A-PD0-Pad114)") (class "Default")
      (node (ref "U18") (pin "114") (pinfunction "PD0_114") (pintype "passive"))
    )
    (net (code "69") (name "unconnected-(U18A-PD1-Pad115)") (class "Default")
      (node (ref "U18") (pin "115") (pinfunction "PD1_115") (pintype "passive"))
    )
    (net (code "70") (name "unconnected-(U18A-PD2-Pad116)") (class "Default")
      (node (ref "U18") (pin "116") (pinfunction "PD2_116") (pintype "passive"))
    )
    (net (code "71") (name "unconnected-(U18A-PD3-Pad117)") (class "Default")
      (node (ref "U18") (pin "117") (pinfunction "PD3_117") (pintype "passive"))
    )
    (net (code "72") (name "unconnected-(U18A-PD4-Pad118)") (class "Default")
      (node (ref "U18") (pin "118") (pinfunction "PD4_118") (pintype "passive"))
    )
    (net (code "73") (name "unconnected-(U18A-PD5-Pad119)") (class "Default")
      (node (ref "U18") (pin "119") (pinfunction "PD5_119") (pintype "passive"))
    )
    (net (code "74") (name "unconnected-(U18A-PD6-Pad122)") (class "Default")
      (node (ref "U18") (pin "122") (pinfunction "PD6_122") (pintype "passive"))
    )
    (net (code "75") (name "unconnected-(U18A-PD7-Pad123)") (class "Default")
      (node (ref "U18") (pin "123") (pinfunction "PD7_123") (pintype "passive"))
    )
    (net (code "76") (name "unconnected-(U18A-PD8-Pad77)") (class "Default")
      (node (ref "U18") (pin "77") (pinfunction "PD8_77") (pintype "passive"))
    )
    (net (code "77") (name "unconnected-(U18A-PD9-Pad78)") (class "Default")
      (node (ref "U18") (pin "78") (pinfunction "PD9_78") (pintype "passive"))
    )
    (net (code "78") (name "unconnected-(U18A-PD10-Pad79)") (class "Default")
      (node (ref "U18") (pin "79") (pinfunction "PD10_79") (pintype "passive"))
    )
    (net (code "79") (name "unconnected-(U18A-PD11-Pad80)") (class "Default")
      (node (ref "U18") (pin "80") (pinfunction "PD11_80") (pintype "passive"))
    )
    (net (code "80") (name "unconnected-(U18A-PD12-Pad81)") (class "Default")
      (node (ref "U18") (pin "81") (pinfunction "PD12_81") (pintype "passive"))
    )
    (net (code "81") (name "unconnected-(U18A-PD13-Pad82)") (class "Default")
      (node (ref "U18") (pin "82") (pinfunction "PD13_82") (pintype "passive"))
    )
    (net (code "82") (name "unconnected-(U18A-PD14-Pad85)") (class "Default")
      (node (ref "U18") (pin "85") (pinfunction "PD14_85") (pintype "passive"))
    )
    (net (code "83") (name "unconnected-(U18A-PD15-Pad86)") (class "Default")
      (node (ref "U18") (pin "86") (pinfunction "PD15_86") (pintype "passive"))
    )
  )
)
